# PLL.net
KiCad netlist of a schematic drawn in Altium Designer
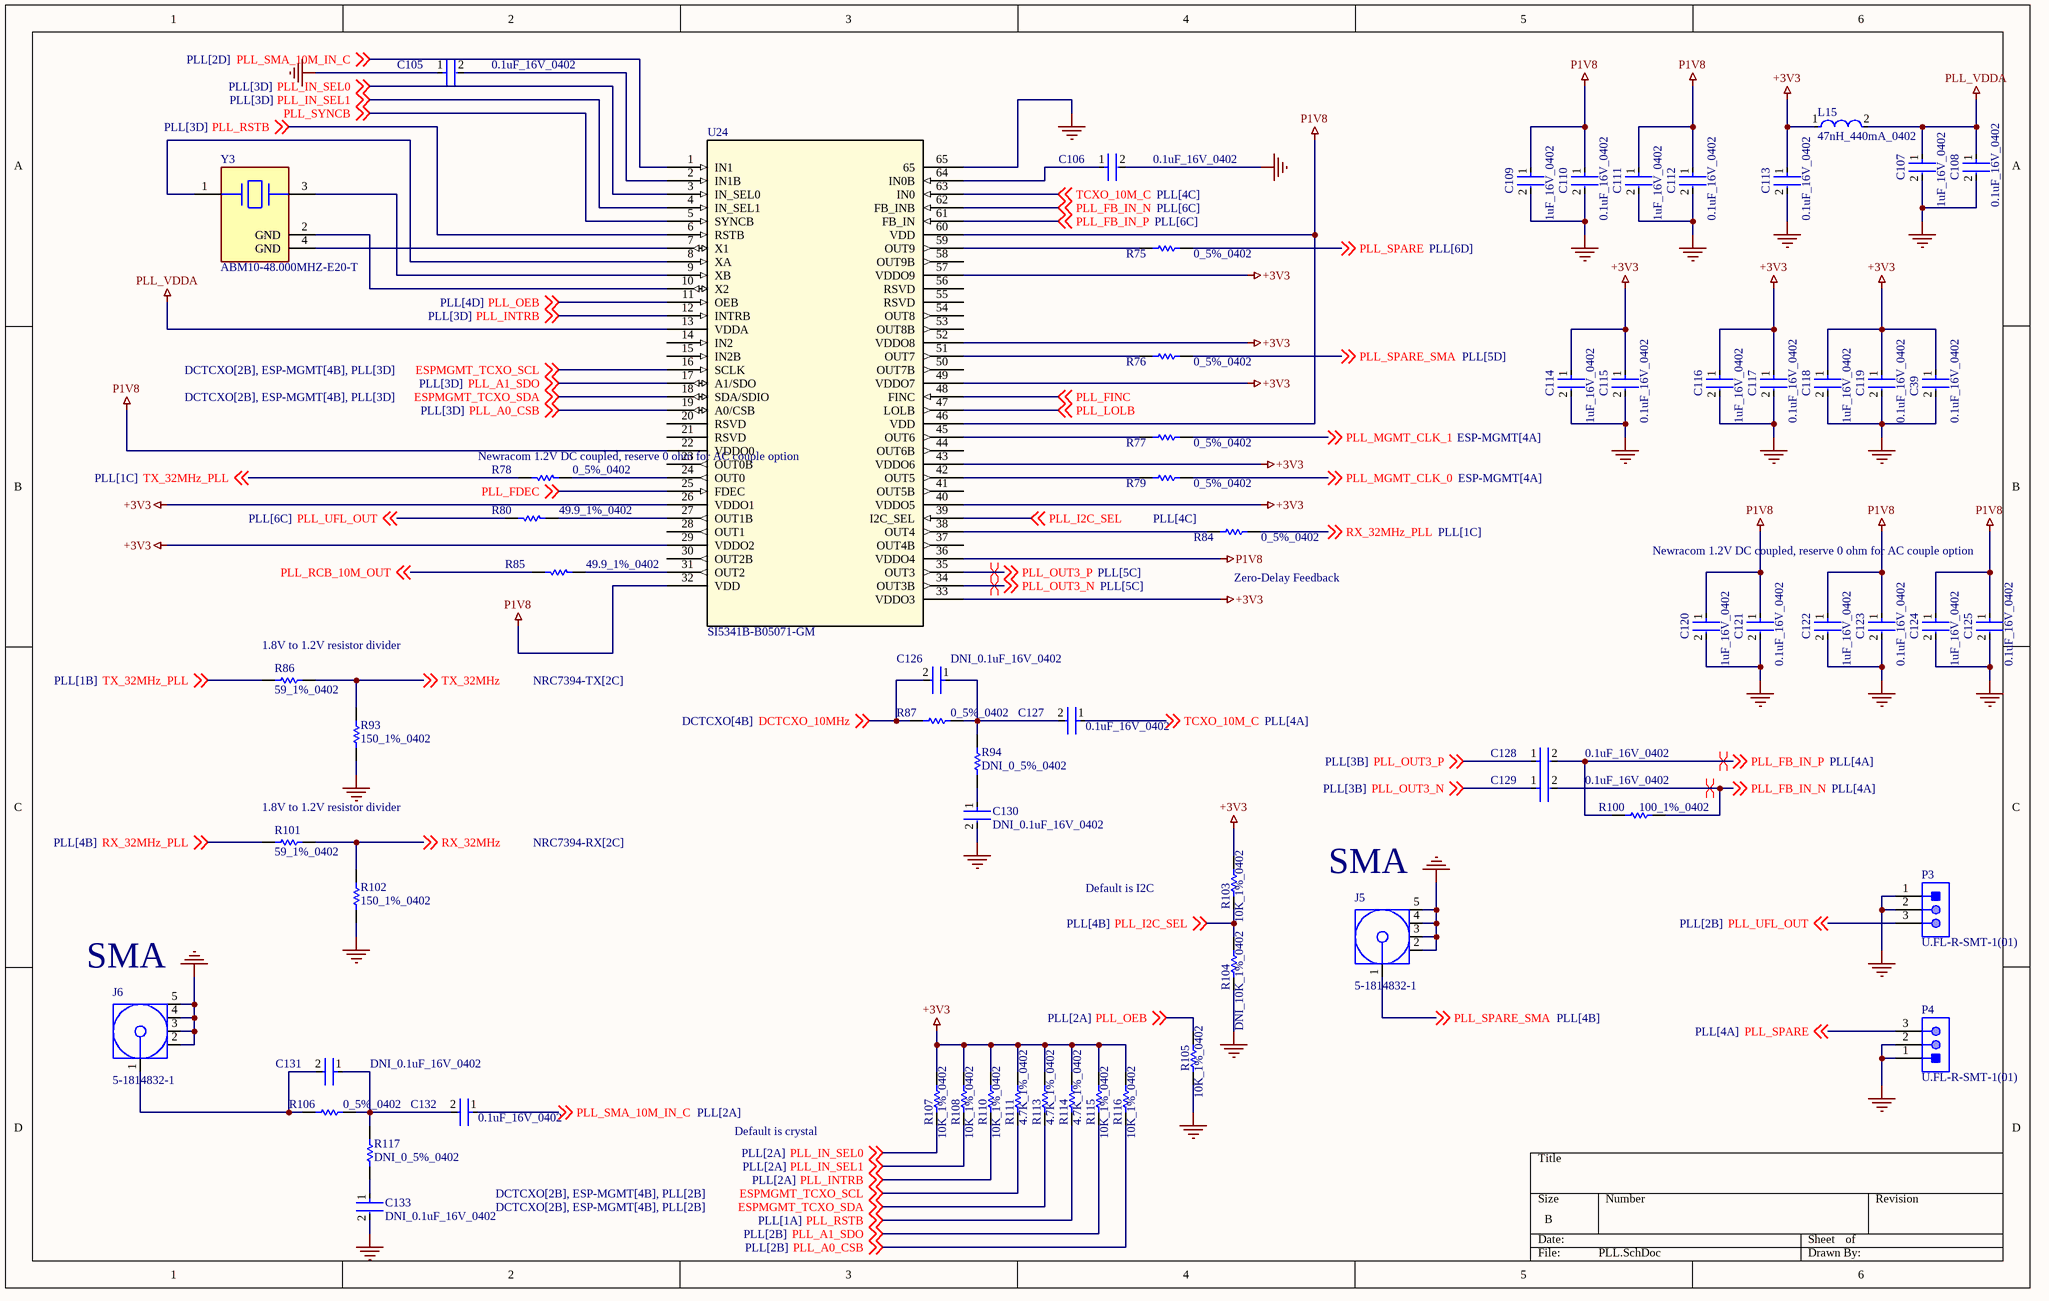
[diagram p0: PLL.SchDoc]

(export (version "E")
  (design (tool "Eeschema 10.0.6"))
  (components
    (comp (ref "C39")
      (value "0.1uF_16V_0402")
      (footprint "FP-C0402-BB-MFG")
      (description "CAP CER 0.1UF 16V 5% X7R 0402")
      (fields
        (field (name "MANUFACTURER") "Kemet")
        (field (name "MANUFACTURER PART NUMBER") "C0402C104J4RACTU")
      )
      (libsource (lib "Altium Content Vault") (part "b4654b650e69147ec39a6b967a45e02"))
    )
    (comp (ref "C105")
      (value "0.1uF_16V_0402")
      (footprint "FP-C0402-BB-MFG")
      (description "CAP CER 0.1UF 16V 5% X7R 0402")
      (fields
        (field (name "MANUFACTURER") "Kemet")
        (field (name "MANUFACTURER PART NUMBER") "C0402C104J4RACTU")
      )
      (libsource (lib "Altium Content Vault") (part "b4654b650e69147ec39a6b967a45e02"))
    )
    (comp (ref "C106")
      (value "0.1uF_16V_0402")
      (footprint "FP-C0402-BB-MFG")
      (description "CAP CER 0.1UF 16V 5% X7R 0402")
      (fields
        (field (name "MANUFACTURER") "Kemet")
        (field (name "MANUFACTURER PART NUMBER") "C0402C104J4RACTU")
      )
      (libsource (lib "Altium Content Vault") (part "b4654b650e69147ec39a6b967a45e02"))
    )
    (comp (ref "C107")
      (value "1uF_16V_0402")
      (footprint "FP-0402-L_1_0_0_05-W_0_5-IPC_A")
      (description "None")
      (fields (field (name "TOLERANCE") "10%"))
      (libsource (lib "Altium Content Vault") (part "b4654b650e69147ec39a6b967a45e02"))
    )
    (comp (ref "C108")
      (value "0.1uF_16V_0402")
      (footprint "FP-C0402-BB-MFG")
      (description "CAP CER 0.1UF 16V 5% X7R 0402")
      (fields
        (field (name "MANUFACTURER") "Kemet")
        (field (name "MANUFACTURER PART NUMBER") "C0402C104J4RACTU")
      )
      (libsource (lib "Altium Content Vault") (part "b4654b650e69147ec39a6b967a45e02"))
    )
    (comp (ref "C109")
      (value "1uF_16V_0402")
      (footprint "FP-0402-L_1_0_0_05-W_0_5-IPC_A")
      (description "None")
      (fields (field (name "TOLERANCE") "10%"))
      (libsource (lib "Altium Content Vault") (part "b4654b650e69147ec39a6b967a45e02"))
    )
    (comp (ref "C110")
      (value "0.1uF_16V_0402")
      (footprint "FP-C0402-BB-MFG")
      (description "CAP CER 0.1UF 16V 5% X7R 0402")
      (fields
        (field (name "MANUFACTURER") "Kemet")
        (field (name "MANUFACTURER PART NUMBER") "C0402C104J4RACTU")
      )
      (libsource (lib "Altium Content Vault") (part "b4654b650e69147ec39a6b967a45e02"))
    )
    (comp (ref "C111")
      (value "1uF_16V_0402")
      (footprint "FP-0402-L_1_0_0_05-W_0_5-IPC_A")
      (description "None")
      (fields (field (name "TOLERANCE") "10%"))
      (libsource (lib "Altium Content Vault") (part "b4654b650e69147ec39a6b967a45e02"))
    )
    (comp (ref "C112")
      (value "0.1uF_16V_0402")
      (footprint "FP-C0402-BB-MFG")
      (description "CAP CER 0.1UF 16V 5% X7R 0402")
      (fields
        (field (name "MANUFACTURER") "Kemet")
        (field (name "MANUFACTURER PART NUMBER") "C0402C104J4RACTU")
      )
      (libsource (lib "Altium Content Vault") (part "b4654b650e69147ec39a6b967a45e02"))
    )
    (comp (ref "C113")
      (value "0.1uF_16V_0402")
      (footprint "FP-C0402-BB-MFG")
      (description "CAP CER 0.1UF 16V 5% X7R 0402")
      (fields
        (field (name "MANUFACTURER") "Kemet")
        (field (name "MANUFACTURER PART NUMBER") "C0402C104J4RACTU")
      )
      (libsource (lib "Altium Content Vault") (part "b4654b650e69147ec39a6b967a45e02"))
    )
    (comp (ref "C114")
      (value "1uF_16V_0402")
      (footprint "FP-0402-L_1_0_0_05-W_0_5-IPC_A")
      (description "None")
      (fields (field (name "TOLERANCE") "10%"))
      (libsource (lib "Altium Content Vault") (part "b4654b650e69147ec39a6b967a45e02"))
    )
    (comp (ref "C115")
      (value "0.1uF_16V_0402")
      (footprint "FP-C0402-BB-MFG")
      (description "CAP CER 0.1UF 16V 5% X7R 0402")
      (fields
        (field (name "MANUFACTURER") "Kemet")
        (field (name "MANUFACTURER PART NUMBER") "C0402C104J4RACTU")
      )
      (libsource (lib "Altium Content Vault") (part "b4654b650e69147ec39a6b967a45e02"))
    )
    (comp (ref "C116")
      (value "1uF_16V_0402")
      (footprint "FP-0402-L_1_0_0_05-W_0_5-IPC_A")
      (description "None")
      (fields (field (name "TOLERANCE") "10%"))
      (libsource (lib "Altium Content Vault") (part "b4654b650e69147ec39a6b967a45e02"))
    )
    (comp (ref "C117")
      (value "0.1uF_16V_0402")
      (footprint "FP-C0402-BB-MFG")
      (description "CAP CER 0.1UF 16V 5% X7R 0402")
      (fields
        (field (name "MANUFACTURER") "Kemet")
        (field (name "MANUFACTURER PART NUMBER") "C0402C104J4RACTU")
      )
      (libsource (lib "Altium Content Vault") (part "b4654b650e69147ec39a6b967a45e02"))
    )
    (comp (ref "C118")
      (value "1uF_16V_0402")
      (footprint "FP-0402-L_1_0_0_05-W_0_5-IPC_A")
      (description "None")
      (fields (field (name "TOLERANCE") "10%"))
      (libsource (lib "Altium Content Vault") (part "b4654b650e69147ec39a6b967a45e02"))
    )
    (comp (ref "C119")
      (value "0.1uF_16V_0402")
      (footprint "FP-C0402-BB-MFG")
      (description "CAP CER 0.1UF 16V 5% X7R 0402")
      (fields
        (field (name "MANUFACTURER") "Kemet")
        (field (name "MANUFACTURER PART NUMBER") "C0402C104J4RACTU")
      )
      (libsource (lib "Altium Content Vault") (part "b4654b650e69147ec39a6b967a45e02"))
    )
    (comp (ref "C120")
      (value "1uF_16V_0402")
      (footprint "FP-0402-L_1_0_0_05-W_0_5-IPC_A")
      (description "None")
      (fields (field (name "TOLERANCE") "10%"))
      (libsource (lib "Altium Content Vault") (part "b4654b650e69147ec39a6b967a45e02"))
    )
    (comp (ref "C121")
      (value "0.1uF_16V_0402")
      (footprint "FP-C0402-BB-MFG")
      (description "CAP CER 0.1UF 16V 5% X7R 0402")
      (fields
        (field (name "MANUFACTURER") "Kemet")
        (field (name "MANUFACTURER PART NUMBER") "C0402C104J4RACTU")
      )
      (libsource (lib "Altium Content Vault") (part "b4654b650e69147ec39a6b967a45e02"))
    )
    (comp (ref "C122")
      (value "1uF_16V_0402")
      (footprint "FP-0402-L_1_0_0_05-W_0_5-IPC_A")
      (description "None")
      (fields (field (name "TOLERANCE") "10%"))
      (libsource (lib "Altium Content Vault") (part "b4654b650e69147ec39a6b967a45e02"))
    )
    (comp (ref "C123")
      (value "0.1uF_16V_0402")
      (footprint "FP-C0402-BB-MFG")
      (description "CAP CER 0.1UF 16V 5% X7R 0402")
      (fields
        (field (name "MANUFACTURER") "Kemet")
        (field (name "MANUFACTURER PART NUMBER") "C0402C104J4RACTU")
      )
      (libsource (lib "Altium Content Vault") (part "b4654b650e69147ec39a6b967a45e02"))
    )
    (comp (ref "C124")
      (value "1uF_16V_0402")
      (footprint "FP-0402-L_1_0_0_05-W_0_5-IPC_A")
      (description "None")
      (fields (field (name "TOLERANCE") "10%"))
      (libsource (lib "Altium Content Vault") (part "b4654b650e69147ec39a6b967a45e02"))
    )
    (comp (ref "C125")
      (value "0.1uF_16V_0402")
      (footprint "FP-C0402-BB-MFG")
      (description "CAP CER 0.1UF 16V 5% X7R 0402")
      (fields
        (field (name "MANUFACTURER") "Kemet")
        (field (name "MANUFACTURER PART NUMBER") "C0402C104J4RACTU")
      )
      (libsource (lib "Altium Content Vault") (part "b4654b650e69147ec39a6b967a45e02"))
    )
    (comp (ref "C126")
      (value "DNI_0.1uF_16V_0402")
      (footprint "FP-C0402-BB-MFG")
      (description "CAP CER 0.1UF 16V 5% X7R 0402")
      (fields
        (field (name "MANUFACTURER") "Kemet")
        (field (name "MANUFACTURER PART NUMBER") "C0402C104J4RACTU")
      )
      (libsource (lib "Altium Content Vault") (part "b4654b650e69147ec39a6b967a45e02"))
    )
    (comp (ref "C127")
      (value "0.1uF_16V_0402")
      (footprint "FP-C0402-BB-MFG")
      (description "CAP CER 0.1UF 16V 5% X7R 0402")
      (fields
        (field (name "MANUFACTURER") "Kemet")
        (field (name "MANUFACTURER PART NUMBER") "C0402C104J4RACTU")
      )
      (libsource (lib "Altium Content Vault") (part "b4654b650e69147ec39a6b967a45e02"))
    )
    (comp (ref "C128")
      (value "0.1uF_16V_0402")
      (footprint "FP-C0402-BB-MFG")
      (description "CAP CER 0.1UF 16V 5% X7R 0402")
      (fields
        (field (name "MANUFACTURER") "Kemet")
        (field (name "MANUFACTURER PART NUMBER") "C0402C104J4RACTU")
      )
      (libsource (lib "Altium Content Vault") (part "b4654b650e69147ec39a6b967a45e02"))
    )
    (comp (ref "C129")
      (value "0.1uF_16V_0402")
      (footprint "FP-C0402-BB-MFG")
      (description "CAP CER 0.1UF 16V 5% X7R 0402")
      (fields
        (field (name "MANUFACTURER") "Kemet")
        (field (name "MANUFACTURER PART NUMBER") "C0402C104J4RACTU")
      )
      (libsource (lib "Altium Content Vault") (part "b4654b650e69147ec39a6b967a45e02"))
    )
    (comp (ref "C130")
      (value "DNI_0.1uF_16V_0402")
      (footprint "FP-C0402-BB-MFG")
      (description "CAP CER 0.1UF 16V 5% X7R 0402")
      (fields
        (field (name "MANUFACTURER") "Kemet")
        (field (name "MANUFACTURER PART NUMBER") "C0402C104J4RACTU")
      )
      (libsource (lib "Altium Content Vault") (part "b4654b650e69147ec39a6b967a45e02"))
    )
    (comp (ref "C131")
      (value "DNI_0.1uF_16V_0402")
      (footprint "FP-C0402-BB-MFG")
      (description "CAP CER 0.1UF 16V 5% X7R 0402")
      (fields
        (field (name "MANUFACTURER") "Kemet")
        (field (name "MANUFACTURER PART NUMBER") "C0402C104J4RACTU")
      )
      (libsource (lib "Altium Content Vault") (part "b4654b650e69147ec39a6b967a45e02"))
    )
    (comp (ref "C132")
      (value "0.1uF_16V_0402")
      (footprint "FP-C0402-BB-MFG")
      (description "CAP CER 0.1UF 16V 5% X7R 0402")
      (fields
        (field (name "MANUFACTURER") "Kemet")
        (field (name "MANUFACTURER PART NUMBER") "C0402C104J4RACTU")
      )
      (libsource (lib "Altium Content Vault") (part "b4654b650e69147ec39a6b967a45e02"))
    )
    (comp (ref "C133")
      (value "DNI_0.1uF_16V_0402")
      (footprint "FP-C0402-BB-MFG")
      (description "CAP CER 0.1UF 16V 5% X7R 0402")
      (fields
        (field (name "MANUFACTURER") "Kemet")
        (field (name "MANUFACTURER PART NUMBER") "C0402C104J4RACTU")
      )
      (libsource (lib "Altium Content Vault") (part "b4654b650e69147ec39a6b967a45e02"))
    )
    (comp (ref "J5")
      (value "5-1814832-1")
      (footprint "TECO-5-1814832-1_V")
      (fields (field (name "MANUFACTURER") "TE Connectivity"))
      (libsource (lib "Altium Content Vault") (part "CN-S-4F-RF5"))
    )
    (comp (ref "J6")
      (value "5-1814832-1")
      (footprint "TECO-5-1814832-1_V")
      (fields (field (name "MANUFACTURER") "TE Connectivity"))
      (libsource (lib "Altium Content Vault") (part "CN-S-4F-RF5"))
    )
    (comp (ref "L15")
      (value "47nH_440mA_0402")
      (footprint "FP-LQW15AN_80-MFG")
      (description "Wire Wound RF Inductor 47nH ±5% 440mA 0.648Ω 0402 (1005)")
      (fields (field (name "TOLERANCE") "5%"))
      (libsource (lib "Altium Content Vault") (part "725321dda6339637d4d059423bc1c3c"))
    )
    (comp (ref "P3")
      (value "U.FL-R-SMT-1(01)")
      (footprint "HRS-U.FL-R-SMT-3_V")
      (description "Ultra Small Coaxial Connector, 6 GHz, -40 to 90 degC, 3-Pin SMD, RoHS, Bulk")
      (fields (field (name "MANUFACTURER") "Hirose Electric"))
      (libsource (lib "Altium Content Vault") (part "CN-1P-M-R3"))
    )
    (comp (ref "P4")
      (value "U.FL-R-SMT-1(01)")
      (footprint "HRS-U.FL-R-SMT-3_V")
      (description "Ultra Small Coaxial Connector, 6 GHz, -40 to 90 degC, 3-Pin SMD, RoHS, Bulk")
      (fields (field (name "MANUFACTURER") "Hirose Electric"))
      (libsource (lib "") (part "CN-1P-M-R3_1"))
    )
    (comp (ref "R75")
      (value "0_5%_0402")
      (footprint "RESC1005X40X25NL05T10")
      (fields (field (name "MANUFACTURER") "Panasonic") (field (name "PART NUMBER") "ERJ-U020R00X"))
      (libsource (lib "Altium Content Vault") (part "RES"))
    )
    (comp (ref "R76")
      (value "0_5%_0402")
      (footprint "RESC1005X40X25NL05T10")
      (fields (field (name "MANUFACTURER") "Panasonic") (field (name "PART NUMBER") "ERJ-U020R00X"))
      (libsource (lib "Altium Content Vault") (part "RES"))
    )
    (comp (ref "R77")
      (value "0_5%_0402")
      (footprint "RESC1005X40X25NL05T10")
      (fields (field (name "MANUFACTURER") "Panasonic") (field (name "PART NUMBER") "ERJ-U020R00X"))
      (libsource (lib "Altium Content Vault") (part "RES"))
    )
    (comp (ref "R78")
      (value "0_5%_0402")
      (footprint "RESC1005X40X25NL05T10")
      (fields (field (name "MANUFACTURER") "Panasonic") (field (name "PART NUMBER") "ERJ-U020R00X"))
      (libsource (lib "Altium Content Vault") (part "RES"))
    )
    (comp (ref "R79")
      (value "0_5%_0402")
      (footprint "RESC1005X40X25NL05T10")
      (fields (field (name "MANUFACTURER") "Panasonic") (field (name "PART NUMBER") "ERJ-U020R00X"))
      (libsource (lib "Altium Content Vault") (part "RES"))
    )
    (comp (ref "R80")
      (value "49.9_1%_0402")
      (footprint "RESC1005X40X25NL10T10")
      (fields (field (name "PART NUMBER") "RK73H1ETTP49R9F") (field (name "MANUFACTURER") "KOA Speer"))
      (libsource (lib "Altium Content Vault") (part "RES"))
    )
    (comp (ref "R84")
      (value "0_5%_0402")
      (footprint "RESC1005X40X25NL05T10")
      (fields (field (name "MANUFACTURER") "Panasonic") (field (name "PART NUMBER") "ERJ-U020R00X"))
      (libsource (lib "Altium Content Vault") (part "RES"))
    )
    (comp (ref "R85")
      (value "49.9_1%_0402")
      (footprint "RESC1005X40X25NL10T10")
      (fields (field (name "PART NUMBER") "RK73H1ETTP49R9F") (field (name "MANUFACTURER") "KOA Speer"))
      (libsource (lib "Altium Content Vault") (part "RES"))
    )
    (comp (ref "R86")
      (value "59_1%_0402")
      (footprint "RESC1005X40X25LL10T10")
      (fields (field (name "PART NUMBER") "CR0402-FX-59R0GLF") (field (name "MANUFACTURER") "Bourns"))
      (libsource (lib "Altium Content Vault") (part "RES"))
    )
    (comp (ref "R87")
      (value "0_5%_0402")
      (footprint "RESC1005X40X25NL05T10")
      (fields (field (name "MANUFACTURER") "Panasonic") (field (name "PART NUMBER") "ERJ-U020R00X"))
      (libsource (lib "Altium Content Vault") (part "RES"))
    )
    (comp (ref "R93")
      (value "150_1%_0402")
      (footprint "RESC1005X40X25NL10T10")
      (fields (field (name "PART NUMBER") "MC00625W04021150R") (field (name "MANUFACTURER") "Multicomp"))
      (libsource (lib "Altium Content Vault") (part "RES"))
    )
    (comp (ref "R94")
      (value "DNI_0_5%_0402")
      (footprint "RESC1005X40X25NL05T10")
      (fields (field (name "MANUFACTURER") "Panasonic") (field (name "PART NUMBER") "ERJ-U020R00X"))
      (libsource (lib "Altium Content Vault") (part "RES"))
    )
    (comp (ref "R100")
      (value "100_1%_0402")
      (footprint "RESC1005X40X25NL05T10")
      (fields (field (name "MANUFACTURER") "Yageo") (field (name "PART NUMBER") "RC0402FR-13100RL"))
      (libsource (lib "Altium Content Vault") (part "RES"))
    )
    (comp (ref "R101")
      (value "59_1%_0402")
      (footprint "RESC1005X40X25LL10T10")
      (fields (field (name "PART NUMBER") "CR0402-FX-59R0GLF") (field (name "MANUFACTURER") "Bourns"))
      (libsource (lib "Altium Content Vault") (part "RES"))
    )
    (comp (ref "R102")
      (value "150_1%_0402")
      (footprint "RESC1005X40X25NL10T10")
      (fields (field (name "PART NUMBER") "MC00625W04021150R") (field (name "MANUFACTURER") "Multicomp"))
      (libsource (lib "Altium Content Vault") (part "RES"))
    )
    (comp (ref "R103")
      (value "10K_1%_0402")
      (footprint "RESC1005X40X25NL10T10")
      (fields (field (name "MANUFACTURER") "Bourns") (field (name "PART NUMBER") "CR0402-FX-1002GLF"))
      (libsource (lib "Altium Content Vault") (part "RES"))
    )
    (comp (ref "R104")
      (value "DNI_10K_1%_0402")
      (footprint "RESC1005X40X25NL10T10")
      (fields (field (name "MANUFACTURER") "Bourns") (field (name "PART NUMBER") "CR0402-FX-1002GLF"))
      (libsource (lib "Altium Content Vault") (part "RES"))
    )
    (comp (ref "R105")
      (value "10K_1%_0402")
      (footprint "RESC1005X40X25NL10T10")
      (fields (field (name "MANUFACTURER") "Bourns") (field (name "PART NUMBER") "CR0402-FX-1002GLF"))
      (libsource (lib "Altium Content Vault") (part "RES"))
    )
    (comp (ref "R106")
      (value "0_5%_0402")
      (footprint "RESC1005X40X25NL05T10")
      (fields (field (name "MANUFACTURER") "Panasonic") (field (name "PART NUMBER") "ERJ-U020R00X"))
      (libsource (lib "Altium Content Vault") (part "RES"))
    )
    (comp (ref "R107")
      (value "10K_1%_0402")
      (footprint "RESC1005X40X25NL10T10")
      (fields (field (name "MANUFACTURER") "Bourns") (field (name "PART NUMBER") "CR0402-FX-1002GLF"))
      (libsource (lib "Altium Content Vault") (part "RES"))
    )
    (comp (ref "R108")
      (value "10K_1%_0402")
      (footprint "RESC1005X40X25NL10T10")
      (fields (field (name "MANUFACTURER") "Bourns") (field (name "PART NUMBER") "CR0402-FX-1002GLF"))
      (libsource (lib "Altium Content Vault") (part "RES"))
    )
    (comp (ref "R110")
      (value "10K_1%_0402")
      (footprint "RESC1005X40X25NL10T10")
      (fields (field (name "MANUFACTURER") "Bourns") (field (name "PART NUMBER") "CR0402-FX-1002GLF"))
      (libsource (lib "Altium Content Vault") (part "RES"))
    )
    (comp (ref "R111")
      (value "4.7K_1%_0402")
      (footprint "RESC1005X40X25NL10T10")
      (fields (field (name "MANUFACTURER") "Bourns") (field (name "PART NUMBER") "CR0402-FX-4701GLF"))
      (libsource (lib "Altium Content Vault") (part "RES"))
    )
    (comp (ref "R113")
      (value "4.7K_1%_0402")
      (footprint "RESC1005X40X25NL10T10")
      (fields (field (name "MANUFACTURER") "Bourns") (field (name "PART NUMBER") "CR0402-FX-4701GLF"))
      (libsource (lib "Altium Content Vault") (part "RES"))
    )
    (comp (ref "R114")
      (value "4.7K_1%_0402")
      (footprint "RESC1005X40X25NL10T10")
      (fields (field (name "MANUFACTURER") "Bourns") (field (name "PART NUMBER") "CR0402-FX-4701GLF"))
      (libsource (lib "Altium Content Vault") (part "RES"))
    )
    (comp (ref "R115")
      (value "10K_1%_0402")
      (footprint "RESC1005X40X25NL10T10")
      (fields (field (name "MANUFACTURER") "Bourns") (field (name "PART NUMBER") "CR0402-FX-1002GLF"))
      (libsource (lib "Altium Content Vault") (part "RES"))
    )
    (comp (ref "R116")
      (value "10K_1%_0402")
      (footprint "RESC1005X40X25NL10T10")
      (fields (field (name "MANUFACTURER") "Bourns") (field (name "PART NUMBER") "CR0402-FX-1002GLF"))
      (libsource (lib "Altium Content Vault") (part "RES"))
    )
    (comp (ref "R117")
      (value "DNI_0_5%_0402")
      (footprint "RESC1005X40X25NL05T10")
      (fields (field (name "MANUFACTURER") "Panasonic") (field (name "PART NUMBER") "ERJ-U020R00X"))
      (libsource (lib "Altium Content Vault") (part "RES"))
    )
    (comp (ref "U24")
      (value "SI5341B-B05071-GM")
      (footprint "QFN64_SI5341_SIL_SKY")
      (description "No Description Available")
      (fields (field (name "COPYRIGHT") "Copyright (C) 2023 Ultra Librarian. All rights reserved."))
      (libsource (lib "SI5341B-B05071-GM") (part "SI5341B-B05071-GM"))
    )
    (comp (ref "Y3")
      (value "ABM10-48.000MHZ-E20-T")
      (footprint "FP-ABM10-MFG")
      (description "Crystal 48MHz ±20ppm 10pF SMD-4 2.5mm x 2mm")
      (fields (field (name "TOLERANCE") "20ppm"))
      (libsource (lib "Altium Content Vault") (part "0934ba461506c7e3a0bb4df7a4ed385"))
    )
  )
  (nets
    (net (code "1") (name "+3V3") (class "Default")
      (node (ref "C113") (pin "1") (pinfunction "1_1") (pintype "passive"))
      (node (ref "C114") (pin "1") (pinfunction "1_1") (pintype "passive"))
      (node (ref "C115") (pin "1") (pinfunction "1_1") (pintype "passive"))
      (node (ref "C116") (pin "1") (pinfunction "1_1") (pintype "passive"))
      (node (ref "C117") (pin "1") (pinfunction "1_1") (pintype "passive"))
      (node (ref "C118") (pin "1") (pinfunction "1_1") (pintype "passive"))
      (node (ref "C119") (pin "1") (pinfunction "1_1") (pintype "passive"))
      (node (ref "C39") (pin "1") (pinfunction "1_1") (pintype "passive"))
      (node (ref "L15") (pin "1") (pinfunction "1_1") (pintype "passive"))
      (node (ref "R103") (pin "2") (pinfunction "2_2") (pintype "passive"))
      (node (ref "R107") (pin "2") (pinfunction "2_2") (pintype "passive"))
      (node (ref "R108") (pin "2") (pinfunction "2_2") (pintype "passive"))
      (node (ref "R110") (pin "2") (pinfunction "2_2") (pintype "passive"))
      (node (ref "R111") (pin "2") (pinfunction "2_2") (pintype "passive"))
      (node (ref "R113") (pin "2") (pinfunction "2_2") (pintype "passive"))
      (node (ref "R114") (pin "2") (pinfunction "2_2") (pintype "passive"))
      (node (ref "R115") (pin "2") (pinfunction "2_2") (pintype "passive"))
      (node (ref "R116") (pin "2") (pinfunction "2_2") (pintype "passive"))
      (node (ref "U24") (pin "26") (pinfunction "VDDO1_26") (pintype "power_in"))
      (node (ref "U24") (pin "29") (pinfunction "VDDO2_29") (pintype "power_in"))
      (node (ref "U24") (pin "33") (pinfunction "VDDO3_33") (pintype "power_in"))
      (node (ref "U24") (pin "40") (pinfunction "VDDO5_40") (pintype "power_in"))
      (node (ref "U24") (pin "43") (pinfunction "VDDO6_43") (pintype "power_in"))
      (node (ref "U24") (pin "49") (pinfunction "VDDO7_49") (pintype "power_in"))
      (node (ref "U24") (pin "52") (pinfunction "VDDO8_52") (pintype "power_in"))
      (node (ref "U24") (pin "57") (pinfunction "VDDO9_57") (pintype "power_in"))
    )
    (net (code "2") (name "DCTCXO_10MHz") (class "Default")
      (node (ref "C126") (pin "2") (pinfunction "2_2") (pintype "passive"))
      (node (ref "R87") (pin "1") (pinfunction "1_1") (pintype "passive"))
    )
    (net (code "3") (name "ESPMGMT_TCXO_SCL") (class "Default")
      (node (ref "R111") (pin "1") (pinfunction "1_1") (pintype "passive"))
      (node (ref "U24") (pin "16") (pinfunction "SCLK_16") (pintype "input"))
    )
    (net (code "4") (name "ESPMGMT_TCXO_SDA") (class "Default")
      (node (ref "R113") (pin "1") (pinfunction "1_1") (pintype "passive"))
      (node (ref "U24") (pin "18") (pinfunction "SDA/SDIO_18") (pintype "bidirectional"))
    )
    (net (code "5") (name "GND") (class "Default")
      (node (ref "C105") (pin "1") (pinfunction "1_1") (pintype "passive"))
      (node (ref "C106") (pin "2") (pinfunction "2_2") (pintype "passive"))
      (node (ref "C107") (pin "2") (pinfunction "2_2") (pintype "passive"))
      (node (ref "C108") (pin "2") (pinfunction "2_2") (pintype "passive"))
      (node (ref "C109") (pin "2") (pinfunction "2_2") (pintype "passive"))
      (node (ref "C110") (pin "2") (pinfunction "2_2") (pintype "passive"))
      (node (ref "C111") (pin "2") (pinfunction "2_2") (pintype "passive"))
      (node (ref "C112") (pin "2") (pinfunction "2_2") (pintype "passive"))
      (node (ref "C113") (pin "2") (pinfunction "2_2") (pintype "passive"))
      (node (ref "C114") (pin "2") (pinfunction "2_2") (pintype "passive"))
      (node (ref "C115") (pin "2") (pinfunction "2_2") (pintype "passive"))
      (node (ref "C116") (pin "2") (pinfunction "2_2") (pintype "passive"))
      (node (ref "C117") (pin "2") (pinfunction "2_2") (pintype "passive"))
      (node (ref "C118") (pin "2") (pinfunction "2_2") (pintype "passive"))
      (node (ref "C119") (pin "2") (pinfunction "2_2") (pintype "passive"))
      (node (ref "C120") (pin "2") (pinfunction "2_2") (pintype "passive"))
      (node (ref "C121") (pin "2") (pinfunction "2_2") (pintype "passive"))
      (node (ref "C122") (pin "2") (pinfunction "2_2") (pintype "passive"))
      (node (ref "C123") (pin "2") (pinfunction "2_2") (pintype "passive"))
      (node (ref "C124") (pin "2") (pinfunction "2_2") (pintype "passive"))
      (node (ref "C125") (pin "2") (pinfunction "2_2") (pintype "passive"))
      (node (ref "C130") (pin "2") (pinfunction "2_2") (pintype "passive"))
      (node (ref "C133") (pin "2") (pinfunction "2_2") (pintype "passive"))
      (node (ref "C39") (pin "2") (pinfunction "2_2") (pintype "passive"))
      (node (ref "J5") (pin "2") (pinfunction "2_2") (pintype "passive"))
      (node (ref "J5") (pin "3") (pinfunction "3_3") (pintype "passive"))
      (node (ref "J5") (pin "4") (pinfunction "4_4") (pintype "passive"))
      (node (ref "J5") (pin "5") (pinfunction "5_5") (pintype "passive"))
      (node (ref "J6") (pin "2") (pinfunction "2_2") (pintype "passive"))
      (node (ref "J6") (pin "3") (pinfunction "3_3") (pintype "passive"))
      (node (ref "J6") (pin "4") (pinfunction "4_4") (pintype "passive"))
      (node (ref "J6") (pin "5") (pinfunction "5_5") (pintype "passive"))
      (node (ref "P3") (pin "1") (pinfunction "1_1") (pintype "passive"))
      (node (ref "P3") (pin "2") (pinfunction "2_2") (pintype "passive"))
      (node (ref "P4") (pin "1") (pinfunction "1_1") (pintype "passive"))
      (node (ref "P4") (pin "2") (pinfunction "2_2") (pintype "passive"))
      (node (ref "R102") (pin "1") (pinfunction "1_1") (pintype "passive"))
      (node (ref "R104") (pin "1") (pinfunction "1_1") (pintype "passive"))
      (node (ref "R105") (pin "1") (pinfunction "1_1") (pintype "passive"))
      (node (ref "R93") (pin "1") (pinfunction "1_1") (pintype "passive"))
      (node (ref "U24") (pin "65") (pinfunction "65_65") (pintype "passive"))
    )
    (net (code "6") (name "Net-(C126-Pad1)") (class "Default")
      (node (ref "C126") (pin "1") (pinfunction "1_1") (pintype "passive"))
      (node (ref "C127") (pin "2") (pinfunction "2_2") (pintype "passive"))
      (node (ref "R87") (pin "2") (pinfunction "2_2") (pintype "passive"))
      (node (ref "R94") (pin "2") (pinfunction "2_2") (pintype "passive"))
    )
    (net (code "7") (name "Net-(C130-Pad1)") (class "Default")
      (node (ref "C130") (pin "1") (pinfunction "1_1") (pintype "passive"))
      (node (ref "R94") (pin "1") (pinfunction "1_1") (pintype "passive"))
    )
    (net (code "8") (name "Net-(C131-Pad1)") (class "Default")
      (node (ref "C131") (pin "1") (pinfunction "1_1") (pintype "passive"))
      (node (ref "C132") (pin "2") (pinfunction "2_2") (pintype "passive"))
      (node (ref "R106") (pin "2") (pinfunction "2_2") (pintype "passive"))
      (node (ref "R117") (pin "2") (pinfunction "2_2") (pintype "passive"))
    )
    (net (code "9") (name "Net-(C131-Pad2)") (class "Default")
      (node (ref "C131") (pin "2") (pinfunction "2_2") (pintype "passive"))
      (node (ref "J6") (pin "1") (pinfunction "1_1") (pintype "passive"))
      (node (ref "R106") (pin "1") (pinfunction "1_1") (pintype "passive"))
    )
    (net (code "10") (name "Net-(C133-Pad1)") (class "Default")
      (node (ref "C133") (pin "1") (pinfunction "1_1") (pintype "passive"))
      (node (ref "R117") (pin "1") (pinfunction "1_1") (pintype "passive"))
    )
    (net (code "11") (name "Net-(U24-IN0B)") (class "Default")
      (node (ref "C106") (pin "1") (pinfunction "1_1") (pintype "passive"))
      (node (ref "U24") (pin "64") (pinfunction "IN0B_64") (pintype "input"))
    )
    (net (code "12") (name "Net-(U24-IN1B)") (class "Default")
      (node (ref "C105") (pin "2") (pinfunction "2_2") (pintype "passive"))
      (node (ref "U24") (pin "2") (pinfunction "IN1B_2") (pintype "input"))
    )
    (net (code "13") (name "Net-(U24-OUT0)") (class "Default")
      (node (ref "R78") (pin "1") (pinfunction "1_1") (pintype "passive"))
      (node (ref "U24") (pin "24") (pinfunction "OUT0_24") (pintype "output"))
    )
    (net (code "14") (name "Net-(U24-OUT1B)") (class "Default")
      (node (ref "R80") (pin "2") (pinfunction "2_2") (pintype "passive"))
      (node (ref "U24") (pin "27") (pinfunction "OUT1B_27") (pintype "output"))
    )
    (net (code "15") (name "Net-(U24-OUT2)") (class "Default")
      (node (ref "R85") (pin "2") (pinfunction "2_2") (pintype "passive"))
      (node (ref "U24") (pin "31") (pinfunction "OUT2_31") (pintype "output"))
    )
    (net (code "16") (name "Net-(U24-OUT4)") (class "Default")
      (node (ref "R84") (pin "1") (pinfunction "1_1") (pintype "passive"))
      (node (ref "U24") (pin "38") (pinfunction "OUT4_38") (pintype "output"))
    )
    (net (code "17") (name "Net-(U24-OUT5)") (class "Default")
      (node (ref "R79") (pin "1") (pinfunction "1_1") (pintype "passive"))
      (node (ref "U24") (pin "42") (pinfunction "OUT5_42") (pintype "output"))
    )
    (net (code "18") (name "Net-(U24-OUT6)") (class "Default")
      (node (ref "R77") (pin "1") (pinfunction "1_1") (pintype "passive"))
      (node (ref "U24") (pin "45") (pinfunction "OUT6_45") (pintype "output"))
    )
    (net (code "19") (name "Net-(U24-OUT7)") (class "Default")
      (node (ref "R76") (pin "1") (pinfunction "1_1") (pintype "passive"))
      (node (ref "U24") (pin "51") (pinfunction "OUT7_51") (pintype "output"))
    )
    (net (code "20") (name "Net-(U24-OUT9)") (class "Default")
      (node (ref "R75") (pin "1") (pinfunction "1_1") (pintype "passive"))
      (node (ref "U24") (pin "59") (pinfunction "OUT9_59") (pintype "output"))
    )
    (net (code "21") (name "Net-(U24-X1)") (class "Default")
      (node (ref "U24") (pin "7") (pinfunction "X1_7") (pintype "bidirectional"))
      (node (ref "Y3") (pin "4") (pinfunction "GND_4") (pintype "power_in"))
    )
    (net (code "22") (name "Net-(U24-X2)") (class "Default")
      (node (ref "U24") (pin "10") (pinfunction "X2_10") (pintype "bidirectional"))
      (node (ref "Y3") (pin "2") (pinfunction "GND_2") (pintype "power_in"))
    )
    (net (code "23") (name "Net-(U24-XA)") (class "Default")
      (node (ref "U24") (pin "8") (pinfunction "XA_8") (pintype "input"))
      (node (ref "Y3") (pin "1") (pinfunction "1_1") (pintype "passive"))
    )
    (net (code "24") (name "Net-(U24-XB)") (class "Default")
      (node (ref "U24") (pin "9") (pinfunction "XB_9") (pintype "input"))
      (node (ref "Y3") (pin "3") (pinfunction "3_3") (pintype "passive"))
    )
    (net (code "25") (name "P1V8") (class "Default")
      (node (ref "C109") (pin "1") (pinfunction "1_1") (pintype "passive"))
      (node (ref "C110") (pin "1") (pinfunction "1_1") (pintype "passive"))
      (node (ref "C111") (pin "1") (pinfunction "1_1") (pintype "passive"))
      (node (ref "C112") (pin "1") (pinfunction "1_1") (pintype "passive"))
      (node (ref "C120") (pin "1") (pinfunction "1_1") (pintype "passive"))
      (node (ref "C121") (pin "1") (pinfunction "1_1") (pintype "passive"))
      (node (ref "C122") (pin "1") (pinfunction "1_1") (pintype "passive"))
      (node (ref "C123") (pin "1") (pinfunction "1_1") (pintype "passive"))
      (node (ref "C124") (pin "1") (pinfunction "1_1") (pintype "passive"))
      (node (ref "C125") (pin "1") (pinfunction "1_1") (pintype "passive"))
      (node (ref "U24") (pin "22") (pinfunction "VDDO0_22") (pintype "power_in"))
      (node (ref "U24") (pin "32") (pinfunction "VDD_32") (pintype "power_in"))
      (node (ref "U24") (pin "36") (pinfunction "VDDO4_36") (pintype "power_in"))
      (node (ref "U24") (pin "46") (pinfunction "VDD_46") (pintype "power_in"))
      (node (ref "U24") (pin "60") (pinfunction "VDD_60") (pintype "power_in"))
    )
    (net (code "26") (name "PLL_A0_CSB") (class "Default")
      (node (ref "R116") (pin "1") (pinfunction "1_1") (pintype "passive"))
      (node (ref "U24") (pin "19") (pinfunction "A0/CSB_19") (pintype "bidirectional"))
    )
    (net (code "27") (name "PLL_A1_SDO") (class "Default")
      (node (ref "R115") (pin "1") (pinfunction "1_1") (pintype "passive"))
      (node (ref "U24") (pin "17") (pinfunction "A1/SDO_17") (pintype "bidirectional"))
    )
    (net (code "28") (name "PLL_FB_IN_N") (class "Default")
      (node (ref "C129") (pin "2") (pinfunction "2_2") (pintype "passive"))
      (node (ref "R100") (pin "2") (pinfunction "2_2") (pintype "passive"))
      (node (ref "U24") (pin "62") (pinfunction "FB_INB_62") (pintype "input"))
    )
    (net (code "29") (name "PLL_FB_IN_P") (class "Default")
      (node (ref "C128") (pin "2") (pinfunction "2_2") (pintype "passive"))
      (node (ref "R100") (pin "1") (pinfunction "1_1") (pintype "passive"))
      (node (ref "U24") (pin "61") (pinfunction "FB_IN_61") (pintype "input"))
    )
    (net (code "30") (name "PLL_FDEC") (class "Default")
      (node (ref "U24") (pin "25") (pinfunction "FDEC_25") (pintype "input"))
    )
    (net (code "31") (name "PLL_FINC") (class "Default")
      (node (ref "U24") (pin "48") (pinfunction "FINC_48") (pintype "input"))
    )
    (net (code "32") (name "PLL_I2C_SEL") (class "Default")
      (node (ref "R103") (pin "1") (pinfunction "1_1") (pintype "passive"))
      (node (ref "R104") (pin "2") (pinfunction "2_2") (pintype "passive"))
      (node (ref "U24") (pin "39") (pinfunction "I2C_SEL_39") (pintype "input"))
    )
    (net (code "33") (name "PLL_INTRB") (class "Default")
      (node (ref "R110") (pin "1") (pinfunction "1_1") (pintype "passive"))
      (node (ref "U24") (pin "12") (pinfunction "INTRB_12") (pintype "input"))
    )
    (net (code "34") (name "PLL_IN_SEL0") (class "Default")
      (node (ref "R107") (pin "1") (pinfunction "1_1") (pintype "passive"))
      (node (ref "U24") (pin "3") (pinfunction "IN_SEL0_3") (pintype "input"))
    )
    (net (code "35") (name "PLL_IN_SEL1") (class "Default")
      (node (ref "R108") (pin "1") (pinfunction "1_1") (pintype "passive"))
      (node (ref "U24") (pin "4") (pinfunction "IN_SEL1_4") (pintype "input"))
    )
    (net (code "36") (name "PLL_LOLB") (class "Default")
      (node (ref "U24") (pin "47") (pinfunction "LOLB_47") (pintype "output"))
    )
    (net (code "37") (name "PLL_MGMT_CLK_0") (class "Default")
      (node (ref "R79") (pin "2") (pinfunction "2_2") (pintype "passive"))
    )
    (net (code "38") (name "PLL_MGMT_CLK_1") (class "Default")
      (node (ref "R77") (pin "2") (pinfunction "2_2") (pintype "passive"))
    )
    (net (code "39") (name "PLL_OEB") (class "Default")
      (node (ref "R105") (pin "2") (pinfunction "2_2") (pintype "passive"))
      (node (ref "U24") (pin "11") (pinfunction "OEB_11") (pintype "input"))
    )
    (net (code "40") (name "PLL_OUT3_N") (class "Default")
      (node (ref "C129") (pin "1") (pinfunction "1_1") (pintype "passive"))
      (node (ref "U24") (pin "34") (pinfunction "OUT3B_34") (pintype "output"))
    )
    (net (code "41") (name "PLL_OUT3_P") (class "Default")
      (node (ref "C128") (pin "1") (pinfunction "1_1") (pintype "passive"))
      (node (ref "U24") (pin "35") (pinfunction "OUT3_35") (pintype "output"))
    )
    (net (code "42") (name "PLL_RCB_10M_OUT") (class "Default")
      (node (ref "R85") (pin "1") (pinfunction "1_1") (pintype "passive"))
    )
    (net (code "43") (name "PLL_RSTB") (class "Default")
      (node (ref "R114") (pin "1") (pinfunction "1_1") (pintype "passive"))
      (node (ref "U24") (pin "6") (pinfunction "RSTB_6") (pintype "input"))
    )
    (net (code "44") (name "PLL_SMA_10M_IN_C") (class "Default")
      (node (ref "C132") (pin "1") (pinfunction "1_1") (pintype "passive"))
      (node (ref "U24") (pin "1") (pinfunction "IN1_1") (pintype "input"))
    )
    (net (code "45") (name "PLL_SPARE") (class "Default")
      (node (ref "P4") (pin "3") (pinfunction "3_3") (pintype "passive"))
      (node (ref "R75") (pin "2") (pinfunction "2_2") (pintype "passive"))
    )
    (net (code "46") (name "PLL_SPARE_SMA") (class "Default")
      (node (ref "J5") (pin "1") (pinfunction "1_1") (pintype "passive"))
      (node (ref "R76") (pin "2") (pinfunction "2_2") (pintype "passive"))
    )
    (net (code "47") (name "PLL_SYNCB") (class "Default")
      (node (ref "U24") (pin "5") (pinfunction "SYNCB_5") (pintype "input"))
    )
    (net (code "48") (name "PLL_UFL_OUT") (class "Default")
      (node (ref "P3") (pin "3") (pinfunction "3_3") (pintype "passive"))
      (node (ref "R80") (pin "1") (pinfunction "1_1") (pintype "passive"))
    )
    (net (code "49") (name "PLL_VDDA") (class "Default")
      (node (ref "C107") (pin "1") (pinfunction "1_1") (pintype "passive"))
      (node (ref "C108") (pin "1") (pinfunction "1_1") (pintype "passive"))
      (node (ref "L15") (pin "2") (pinfunction "2_2") (pintype "passive"))
      (node (ref "U24") (pin "13") (pinfunction "VDDA_13") (pintype "power_in"))
    )
    (net (code "50") (name "RX_32MHz") (class "Default")
      (node (ref "R101") (pin "2") (pinfunction "2_2") (pintype "passive"))
      (node (ref "R102") (pin "2") (pinfunction "2_2") (pintype "passive"))
    )
    (net (code "51") (name "RX_32MHz_PLL") (class "Default")
      (node (ref "R101") (pin "1") (pinfunction "1_1") (pintype "passive"))
      (node (ref "R84") (pin "2") (pinfunction "2_2") (pintype "passive"))
    )
    (net (code "52") (name "TCXO_10M_C") (class "Default")
      (node (ref "C127") (pin "1") (pinfunction "1_1") (pintype "passive"))
      (node (ref "U24") (pin "63") (pinfunction "IN0_63") (pintype "input"))
    )
    (net (code "53") (name "TX_32MHz") (class "Default")
      (node (ref "R86") (pin "2") (pinfunction "2_2") (pintype "passive"))
      (node (ref "R93") (pin "2") (pinfunction "2_2") (pintype "passive"))
    )
    (net (code "54") (name "TX_32MHz_PLL") (class "Default")
      (node (ref "R78") (pin "2") (pinfunction "2_2") (pintype "passive"))
      (node (ref "R86") (pin "1") (pinfunction "1_1") (pintype "passive"))
    )
    (net (code "55") (name "unconnected-(U24-IN2-Pad14)") (class "Default")
      (node (ref "U24") (pin "14") (pinfunction "IN2_14") (pintype "input"))
    )
    (net (code "56") (name "unconnected-(U24-IN2B-Pad15)") (class "Default")
      (node (ref "U24") (pin "15") (pinfunction "IN2B_15") (pintype "input"))
    )
    (net (code "57") (name "unconnected-(U24-OUT0B-Pad23)") (class "Default")
      (node (ref "U24") (pin "23") (pinfunction "OUT0B_23") (pintype "output"))
    )
    (net (code "58") (name "unconnected-(U24-OUT1-Pad28)") (class "Default")
      (node (ref "U24") (pin "28") (pinfunction "OUT1_28") (pintype "output"))
    )
    (net (code "59") (name "unconnected-(U24-OUT2B-Pad30)") (class "Default")
      (node (ref "U24") (pin "30") (pinfunction "OUT2B_30") (pintype "output"))
    )
    (net (code "60") (name "unconnected-(U24-OUT4B-Pad37)") (class "Default")
      (node (ref "U24") (pin "37") (pinfunction "OUT4B_37") (pintype "output"))
    )
    (net (code "61") (name "unconnected-(U24-OUT5B-Pad41)") (class "Default")
      (node (ref "U24") (pin "41") (pinfunction "OUT5B_41") (pintype "output"))
    )
    (net (code "62") (name "unconnected-(U24-OUT6B-Pad44)") (class "Default")
      (node (ref "U24") (pin "44") (pinfunction "OUT6B_44") (pintype "output"))
    )
    (net (code "63") (name "unconnected-(U24-OUT7B-Pad50)") (class "Default")
      (node (ref "U24") (pin "50") (pinfunction "OUT7B_50") (pintype "output"))
    )
    (net (code "64") (name "unconnected-(U24-OUT8-Pad54)") (class "Default")
      (node (ref "U24") (pin "54") (pinfunction "OUT8_54") (pintype "output"))
    )
    (net (code "65") (name "unconnected-(U24-OUT8B-Pad53)") (class "Default")
      (node (ref "U24") (pin "53") (pinfunction "OUT8B_53") (pintype "output"))
    )
    (net (code "66") (name "unconnected-(U24-OUT9B-Pad58)") (class "Default")
      (node (ref "U24") (pin "58") (pinfunction "OUT9B_58") (pintype "output"))
    )
    (net (code "67") (name "unconnected-(U24-RSVD-Pad20)") (class "Default")
      (node (ref "U24") (pin "20") (pinfunction "RSVD_20") (pintype "passive"))
    )
    (net (code "68") (name "unconnected-(U24-RSVD-Pad21)") (class "Default")
      (node (ref "U24") (pin "21") (pinfunction "RSVD_21") (pintype "passive"))
    )
    (net (code "69") (name "unconnected-(U24-RSVD-Pad55)") (class "Default")
      (node (ref "U24") (pin "55") (pinfunction "RSVD_55") (pintype "passive"))
    )
    (net (code "70") (name "unconnected-(U24-RSVD-Pad56)") (class "Default")
      (node (ref "U24") (pin "56") (pinfunction "RSVD_56") (pintype "passive"))
    )
  )
)
